# LT-33222-L_v1_0.net
KiCad netlist of a schematic drawn in EAGLE
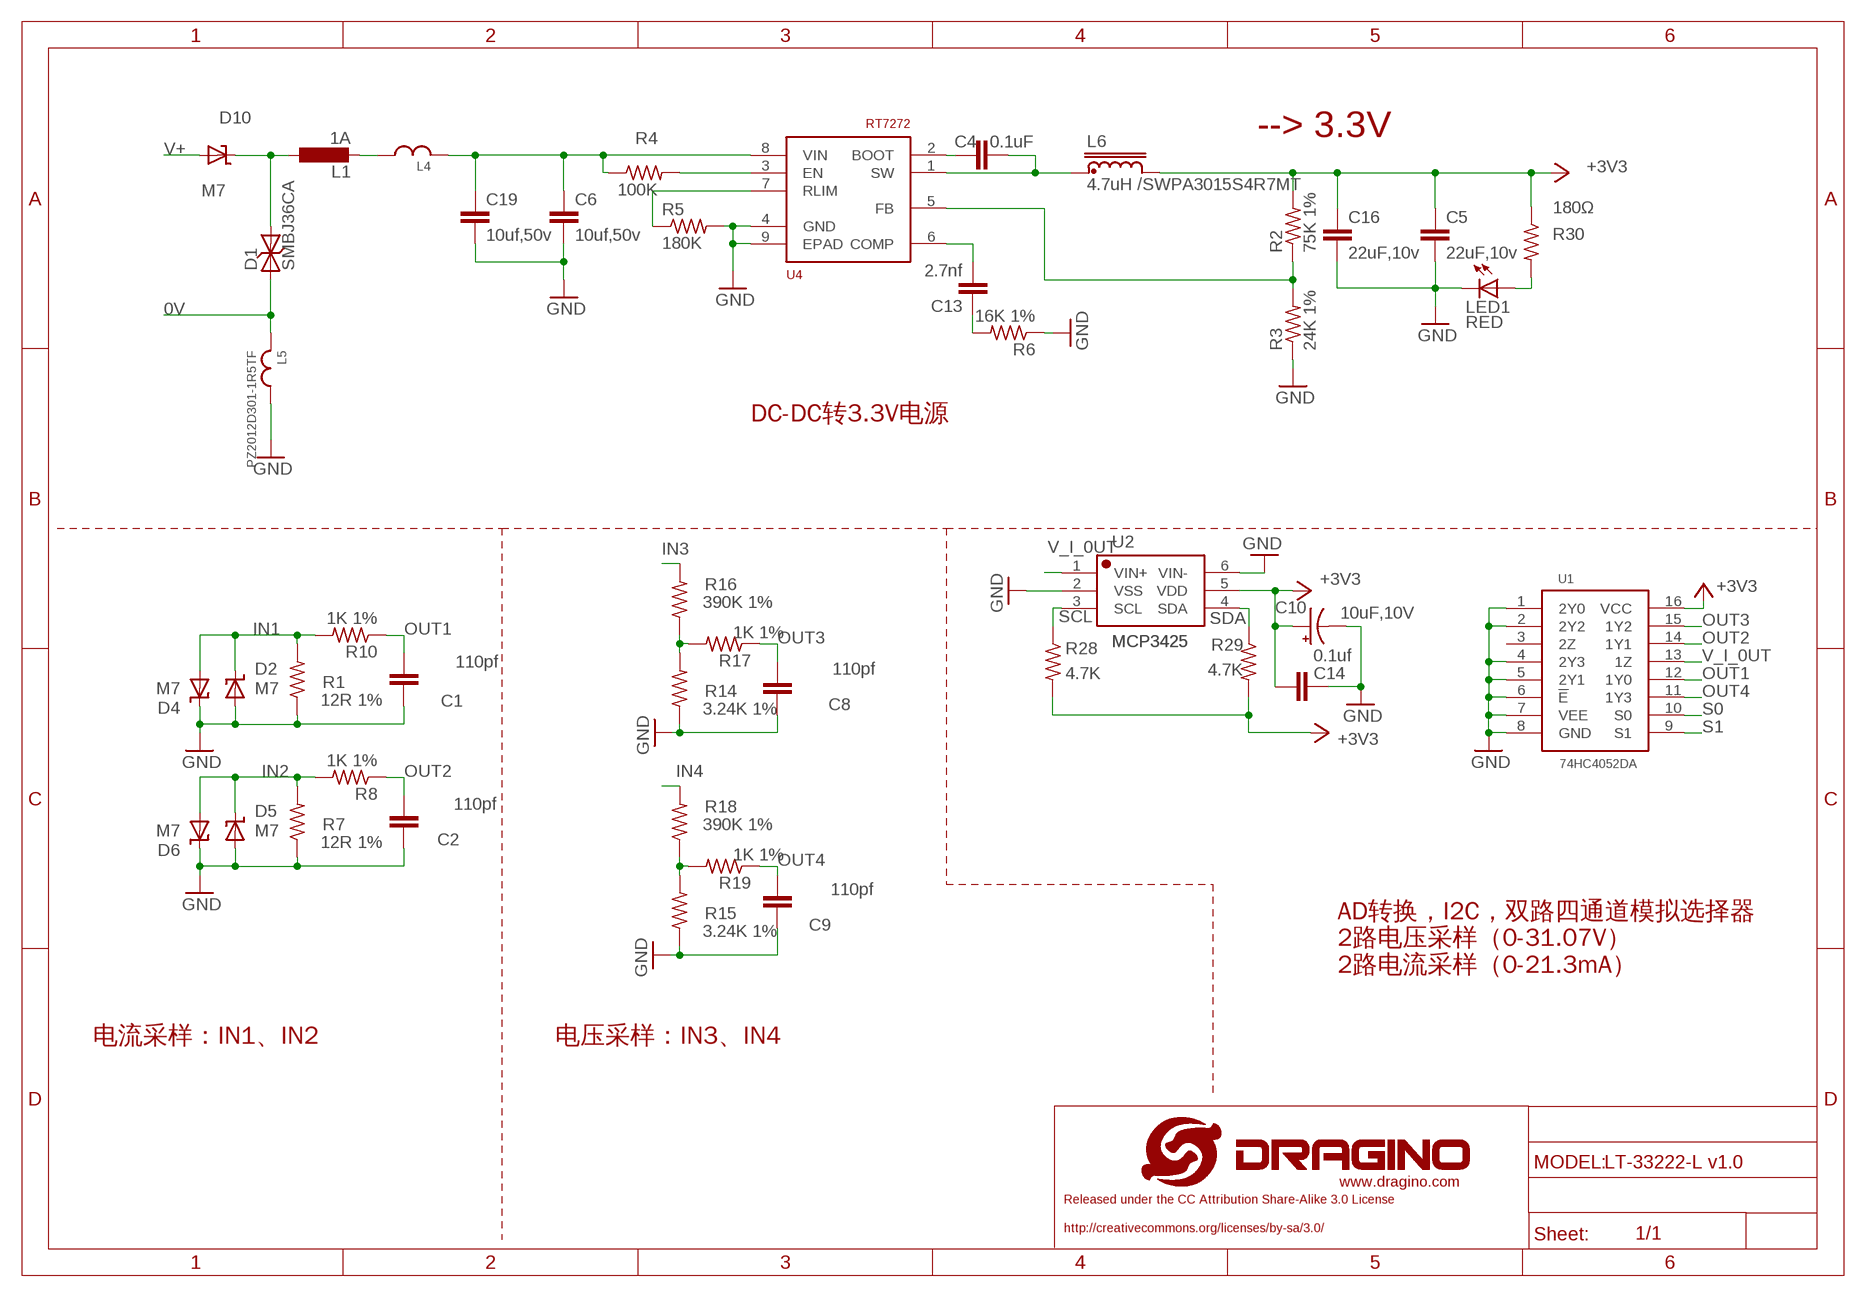
[diagram p0: schematic, sheet 1, part 1 of 2]
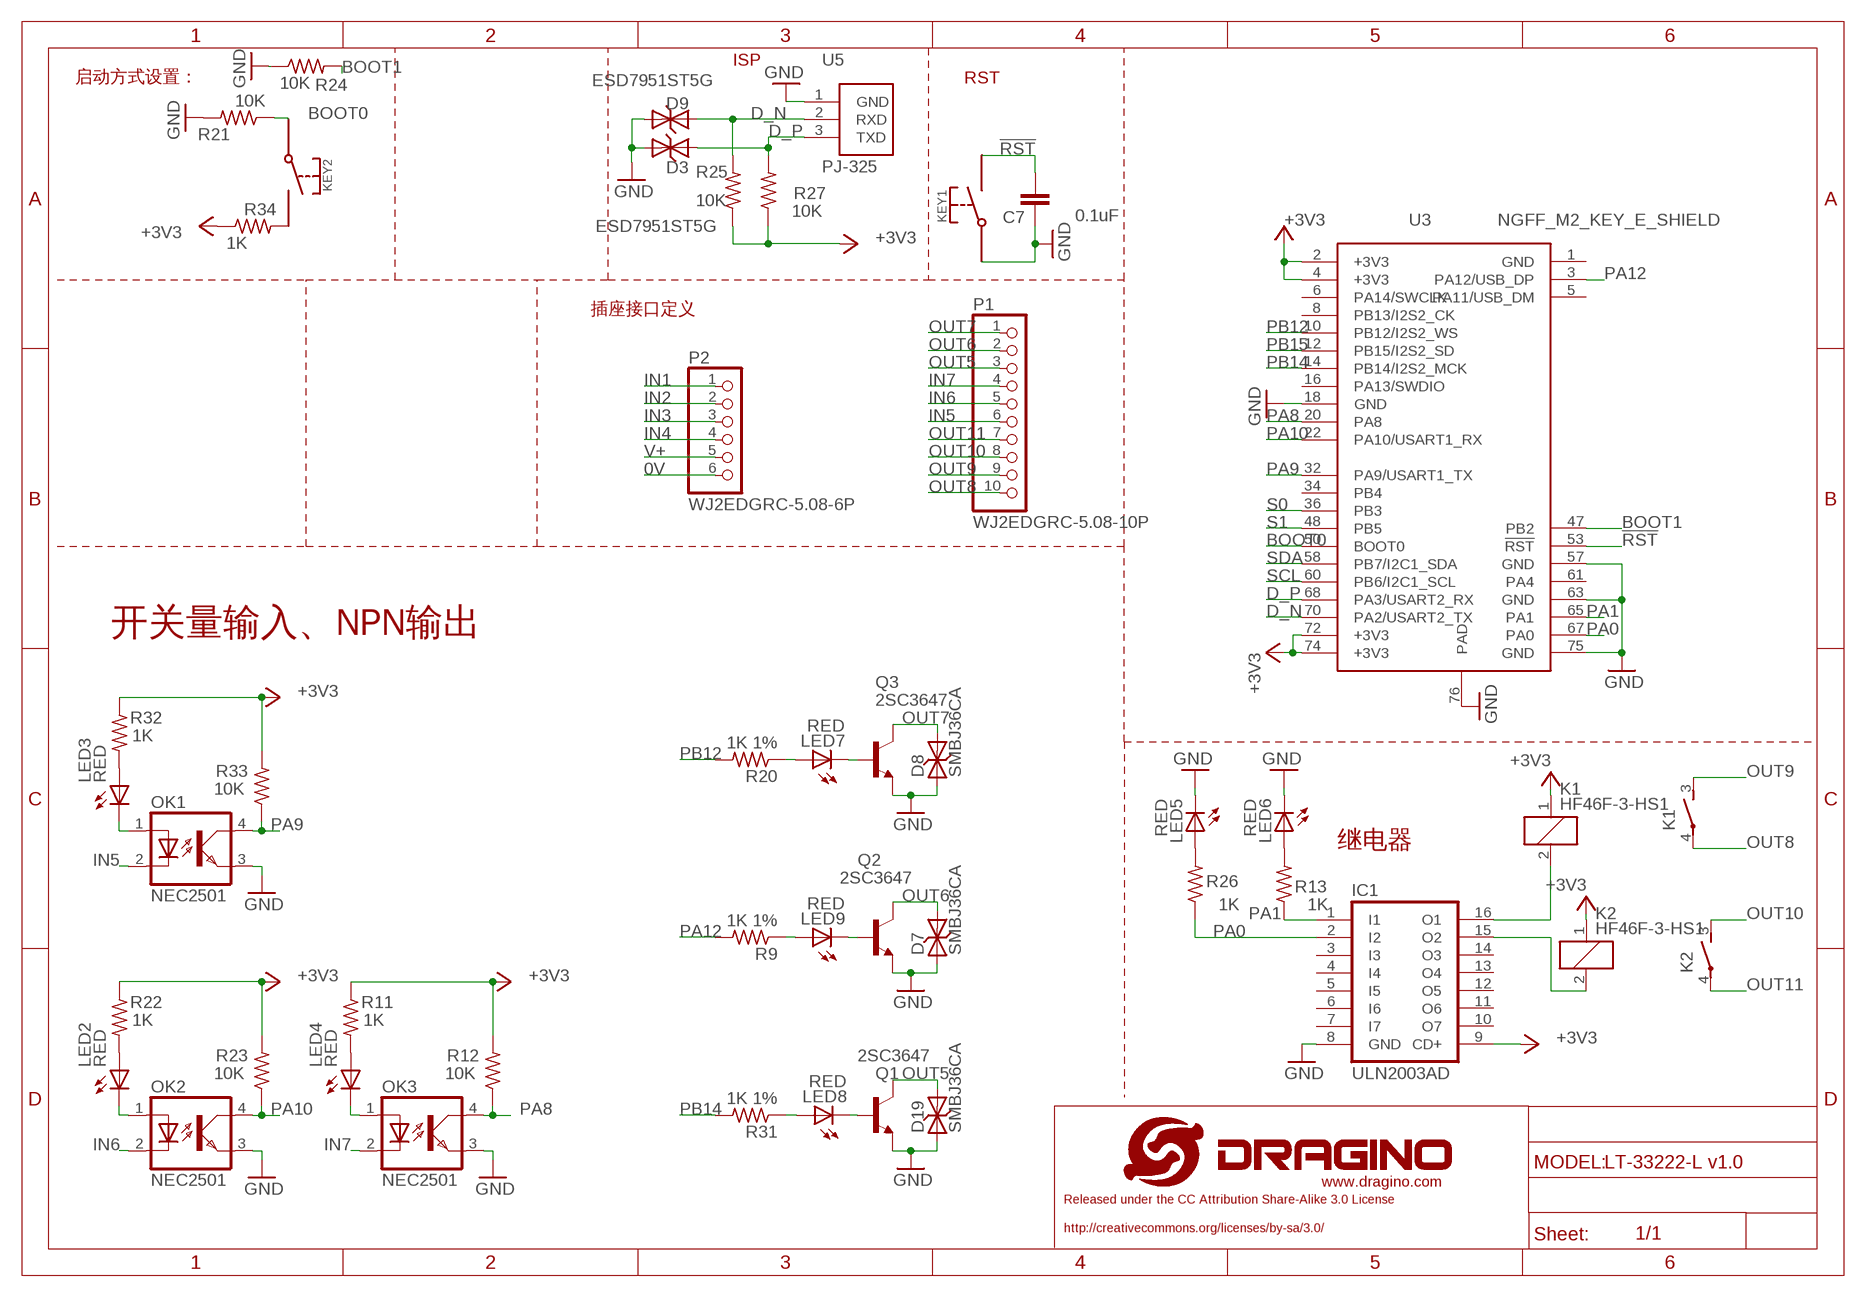
[diagram p1: schematic, sheet 1, part 2 of 2]

(export (version "E")
  (design (tool "Eeschema 10.0.6"))
  (components
    (comp (ref "C1")
      (value "110pf")
      (footprint "eagle-import:C0402")
      (libsource (lib "eagle-import") (part "C-EUC0402"))
    )
    (comp (ref "C2")
      (value "110pf")
      (footprint "eagle-import:C0402")
      (libsource (lib "eagle-import") (part "C-EUC0402"))
    )
    (comp (ref "C4")
      (value "0.1uF")
      (footprint "eagle-import:C0402")
      (libsource (lib "eagle-import") (part "C-EUC0402"))
    )
    (comp (ref "C5")
      (value "22uF,10v")
      (footprint "eagle-import:C1210")
      (libsource (lib "eagle-import") (part "C-EUC1210"))
    )
    (comp (ref "C6")
      (value "10uf,50v")
      (footprint "eagle-import:C1206")
      (libsource (lib "eagle-import") (part "C-EUC1206"))
    )
    (comp (ref "C7")
      (value "0.1uF")
      (footprint "eagle-import:C0402")
      (libsource (lib "eagle-import") (part "C-EUC0402"))
    )
    (comp (ref "C8")
      (value "110pf")
      (footprint "eagle-import:C0402")
      (libsource (lib "eagle-import") (part "C-EUC0402"))
    )
    (comp (ref "C9")
      (value "110pf")
      (footprint "eagle-import:C0402")
      (libsource (lib "eagle-import") (part "C-EUC0402"))
    )
    (comp (ref "C10")
      (value "10uF,10V")
      (footprint "eagle-import:SMC_A")
      (libsource (lib "eagle-import") (part "CPOL-USSMCA"))
    )
    (comp (ref "C13")
      (value "2.7nf")
      (footprint "eagle-import:C0402")
      (libsource (lib "eagle-import") (part "C-EUC0402"))
    )
    (comp (ref "C14")
      (value "0.1uf")
      (footprint "eagle-import:C0402")
      (libsource (lib "eagle-import") (part "C-EUC0402"))
    )
    (comp (ref "C16")
      (value "22uF,10v")
      (footprint "eagle-import:C1210")
      (libsource (lib "eagle-import") (part "C-EUC1210"))
    )
    (comp (ref "C19")
      (value "10uf,50v")
      (footprint "eagle-import:C1206")
      (libsource (lib "eagle-import") (part "C-EUC1206"))
    )
    (comp (ref "D1")
      (value "SMBJ36CA")
      (footprint "eagle-import:DO-214AA")
      (libsource (lib "eagle-import") (part "TVSDIO-214AA"))
    )
    (comp (ref "D2")
      (value "M7")
      (footprint "eagle-import:DO214AC")
      (libsource (lib "eagle-import") (part "SCHOTTKYSMBG"))
    )
    (comp (ref "D3")
      (value "ESD7951ST5G")
      (footprint "eagle-import:SOD−923")
      (libsource (lib "eagle-import") (part "TVSSOD−923"))
    )
    (comp (ref "D4")
      (value "M7")
      (footprint "eagle-import:DO214AC")
      (libsource (lib "eagle-import") (part "SCHOTTKYSMBG"))
    )
    (comp (ref "D5")
      (value "M7")
      (footprint "eagle-import:DO214AC")
      (libsource (lib "eagle-import") (part "SCHOTTKYSMBG"))
    )
    (comp (ref "D6")
      (value "M7")
      (footprint "eagle-import:DO214AC")
      (libsource (lib "eagle-import") (part "SCHOTTKYSMBG"))
    )
    (comp (ref "D7")
      (value "SMBJ36CA")
      (footprint "eagle-import:DO-214AA")
      (libsource (lib "eagle-import") (part "TVSDIO-214AA"))
    )
    (comp (ref "D8")
      (value "SMBJ36CA")
      (footprint "eagle-import:DO-214AA")
      (libsource (lib "eagle-import") (part "TVSDIO-214AA"))
    )
    (comp (ref "D9")
      (value "ESD7951ST5G")
      (footprint "eagle-import:SOD−923")
      (libsource (lib "eagle-import") (part "TVSSOD−923"))
    )
    (comp (ref "D10")
      (value "M7")
      (footprint "eagle-import:DO214AC")
      (libsource (lib "eagle-import") (part "SCHOTTKYSMBG"))
    )
    (comp (ref "D19")
      (value "SMBJ36CA")
      (footprint "eagle-import:DO-214AA")
      (libsource (lib "eagle-import") (part "TVSDIO-214AA"))
    )
    (comp (ref "IC1")
      (value "ULN2003AD")
      (footprint "eagle-import:SO16")
      (libsource (lib "eagle-import") (part "ULN2003AD"))
    )
    (comp (ref "K1")
      (value "HF46F-3-HS1")
      (footprint "eagle-import:HF46F-3-HS1")
      (libsource (lib "eagle-import") (part "HF46F-3-HS1"))
    )
    (comp (ref "K2")
      (value "HF46F-3-HS1")
      (footprint "eagle-import:HF46F-3-HS1")
      (libsource (lib "eagle-import") (part "HF46F-3-HS1"))
    )
    (comp (ref "KEY1")
      (value "SWITCHDIL4")
      (footprint "eagle-import:SWITCH_6X6X19_DIL4")
      (libsource (lib "eagle-import") (part "SWITCHDIL4"))
    )
    (comp (ref "KEY2")
      (value "SWITCHDIL4")
      (footprint "eagle-import:SWITCH_6X6X19_DIL4")
      (libsource (lib "eagle-import") (part "SWITCHDIL4"))
    )
    (comp (ref "L1")
      (value "1A")
      (footprint "eagle-import:L1812")
      (libsource (lib "eagle-import") (part "L-EUL1812"))
    )
    (comp (ref "L4")
      (value "PZ2012D301-1R5TF")
      (footprint "eagle-import:C2012")
      (libsource (lib "eagle-import") (part "BEADS"))
    )
    (comp (ref "L5")
      (value "PZ2012D301-1R5TF")
      (footprint "eagle-import:C0805")
      (libsource (lib "eagle-import") (part "BEADS0805"))
    )
    (comp (ref "L6")
      (value "4.7uH /SWPA3015S4R7MT")
      (footprint "eagle-import:SWPA3010S")
      (libsource (lib "eagle-import") (part "INDUCTORSWPA3010S"))
    )
    (comp (ref "LED1")
      (value "RED")
      (footprint "eagle-import:LED3MM")
      (libsource (lib "eagle-import") (part "LED3MM"))
    )
    (comp (ref "LED2")
      (value "RED")
      (footprint "eagle-import:LED3MM")
      (libsource (lib "eagle-import") (part "LED3MM"))
    )
    (comp (ref "LED3")
      (value "RED")
      (footprint "eagle-import:LED3MM")
      (libsource (lib "eagle-import") (part "LED3MM"))
    )
    (comp (ref "LED4")
      (value "RED")
      (footprint "eagle-import:LED3MM")
      (libsource (lib "eagle-import") (part "LED3MM"))
    )
    (comp (ref "LED5")
      (value "RED")
      (footprint "eagle-import:LED3MM")
      (libsource (lib "eagle-import") (part "LED3MM"))
    )
    (comp (ref "LED6")
      (value "RED")
      (footprint "eagle-import:LED3MM")
      (libsource (lib "eagle-import") (part "LED3MM"))
    )
    (comp (ref "LED7")
      (value "RED")
      (footprint "eagle-import:LED3MM")
      (libsource (lib "eagle-import") (part "LED3MM"))
    )
    (comp (ref "LED8")
      (value "RED")
      (footprint "eagle-import:LED3MM")
      (libsource (lib "eagle-import") (part "LED3MM"))
    )
    (comp (ref "LED9")
      (value "RED")
      (footprint "eagle-import:LED3MM")
      (libsource (lib "eagle-import") (part "LED3MM"))
    )
    (comp (ref "OK1")
      (value "NEC2501")
      (footprint "eagle-import:DIP4")
      (libsource (lib "eagle-import") (part "NEC2501"))
    )
    (comp (ref "OK2")
      (value "NEC2501")
      (footprint "eagle-import:DIP4")
      (libsource (lib "eagle-import") (part "NEC2501"))
    )
    (comp (ref "OK3")
      (value "NEC2501")
      (footprint "eagle-import:DIP4")
      (libsource (lib "eagle-import") (part "NEC2501"))
    )
    (comp (ref "P1")
      (value "WJ2EDGRC-5.08-10P")
      (footprint "eagle-import:WJ2EDGRC-5.08-10P")
      (libsource (lib "eagle-import") (part "WJ2EDGRC-5.08-10P"))
    )
    (comp (ref "P2")
      (value "WJ2EDGRC-5.08-6P")
      (footprint "eagle-import:WJ2EDGRC-5.08-6P")
      (libsource (lib "eagle-import") (part "WJ2EDGRC-5.08-6P"))
    )
    (comp (ref "Q1")
      (value "2SC3647")
      (footprint "eagle-import:SOT-89")
      (libsource (lib "eagle-import") (part "2SC3647"))
    )
    (comp (ref "Q2")
      (value "2SC3647")
      (footprint "eagle-import:SOT-89")
      (libsource (lib "eagle-import") (part "2SC3647"))
    )
    (comp (ref "Q3")
      (value "2SC3647")
      (footprint "eagle-import:SOT-89")
      (libsource (lib "eagle-import") (part "2SC3647"))
    )
    (comp (ref "R1")
      (value "12R 1%")
      (footprint "eagle-import:R1206")
      (libsource (lib "eagle-import") (part "R-US_R1206"))
    )
    (comp (ref "R2")
      (value "75K 1%")
      (footprint "eagle-import:R0402")
      (libsource (lib "eagle-import") (part "R-US_R0402"))
    )
    (comp (ref "R3")
      (value "24K 1%")
      (footprint "eagle-import:R0402")
      (libsource (lib "eagle-import") (part "R-US_R0402"))
    )
    (comp (ref "R4")
      (value "100K")
      (footprint "eagle-import:R0402")
      (libsource (lib "eagle-import") (part "R-US_R0402"))
    )
    (comp (ref "R5")
      (value "180K")
      (footprint "eagle-import:R0402")
      (libsource (lib "eagle-import") (part "R-US_R0402"))
    )
    (comp (ref "R6")
      (value "16K 1%")
      (footprint "eagle-import:R0402")
      (libsource (lib "eagle-import") (part "R-US_R0402"))
    )
    (comp (ref "R7")
      (value "12R 1%")
      (footprint "eagle-import:R1206")
      (libsource (lib "eagle-import") (part "R-US_R1206"))
    )
    (comp (ref "R8")
      (value "1K 1%")
      (footprint "eagle-import:R0402")
      (libsource (lib "eagle-import") (part "R-US_R0402"))
    )
    (comp (ref "R9")
      (value "1K 1%")
      (footprint "eagle-import:R0402")
      (libsource (lib "eagle-import") (part "R-US_R0402"))
    )
    (comp (ref "R10")
      (value "1K 1%")
      (footprint "eagle-import:R0402")
      (libsource (lib "eagle-import") (part "R-US_R0402"))
    )
    (comp (ref "R11")
      (value "1K")
      (footprint "eagle-import:R0402")
      (libsource (lib "eagle-import") (part "R-US_R0402"))
    )
    (comp (ref "R12")
      (value "10K")
      (footprint "eagle-import:R0402")
      (libsource (lib "eagle-import") (part "R-US_R0402"))
    )
    (comp (ref "R13")
      (value "1K")
      (footprint "eagle-import:R0402")
      (libsource (lib "eagle-import") (part "R-US_R0402"))
    )
    (comp (ref "R14")
      (value "3.24K 1%")
      (footprint "eagle-import:R1206")
      (libsource (lib "eagle-import") (part "R-US_R1206"))
    )
    (comp (ref "R15")
      (value "3.24K 1%")
      (footprint "eagle-import:R1206")
      (libsource (lib "eagle-import") (part "R-US_R1206"))
    )
    (comp (ref "R16")
      (value "390K 1%")
      (footprint "eagle-import:R1206")
      (libsource (lib "eagle-import") (part "R-US_R1206"))
    )
    (comp (ref "R17")
      (value "1K 1%")
      (footprint "eagle-import:R0402")
      (libsource (lib "eagle-import") (part "R-US_R0402"))
    )
    (comp (ref "R18")
      (value "390K 1%")
      (footprint "eagle-import:R1206")
      (libsource (lib "eagle-import") (part "R-US_R1206"))
    )
    (comp (ref "R19")
      (value "1K 1%")
      (footprint "eagle-import:R0402")
      (libsource (lib "eagle-import") (part "R-US_R0402"))
    )
    (comp (ref "R20")
      (value "1K 1%")
      (footprint "eagle-import:R0402")
      (libsource (lib "eagle-import") (part "R-US_R0402"))
    )
    (comp (ref "R21")
      (value "10K")
      (footprint "eagle-import:R0402")
      (libsource (lib "eagle-import") (part "R-US_R0402"))
    )
    (comp (ref "R22")
      (value "1K")
      (footprint "eagle-import:R0402")
      (libsource (lib "eagle-import") (part "R-US_R0402"))
    )
    (comp (ref "R23")
      (value "10K")
      (footprint "eagle-import:R0402")
      (libsource (lib "eagle-import") (part "R-US_R0402"))
    )
    (comp (ref "R24")
      (value "10K")
      (footprint "eagle-import:R0402")
      (libsource (lib "eagle-import") (part "R-US_R0402"))
    )
    (comp (ref "R25")
      (value "10K")
      (footprint "eagle-import:R0402")
      (libsource (lib "eagle-import") (part "R-US_R0402"))
    )
    (comp (ref "R26")
      (value "1K")
      (footprint "eagle-import:R0402")
      (libsource (lib "eagle-import") (part "R-US_R0402"))
    )
    (comp (ref "R27")
      (value "10K")
      (footprint "eagle-import:R0402")
      (libsource (lib "eagle-import") (part "R-US_R0402"))
    )
    (comp (ref "R28")
      (value "4.7K")
      (footprint "eagle-import:R0402")
      (libsource (lib "eagle-import") (part "R-US_R0402"))
    )
    (comp (ref "R29")
      (value "4.7K")
      (footprint "eagle-import:R0402")
      (libsource (lib "eagle-import") (part "R-US_R0402"))
    )
    (comp (ref "R30")
      (value "180Ω")
      (footprint "eagle-import:R0402")
      (libsource (lib "eagle-import") (part "R-US_R0402"))
    )
    (comp (ref "R31")
      (value "1K 1%")
      (footprint "eagle-import:R0402")
      (libsource (lib "eagle-import") (part "R-US_R0402"))
    )
    (comp (ref "R32")
      (value "1K")
      (footprint "eagle-import:R0402")
      (libsource (lib "eagle-import") (part "R-US_R0402"))
    )
    (comp (ref "R33")
      (value "10K")
      (footprint "eagle-import:R0402")
      (libsource (lib "eagle-import") (part "R-US_R0402"))
    )
    (comp (ref "R34")
      (value "1K")
      (footprint "eagle-import:R0402")
      (libsource (lib "eagle-import") (part "R-US_R0402"))
    )
    (comp (ref "U1")
      (value "74HC4052DA")
      (footprint "eagle-import:SO16")
      (libsource (lib "eagle-import") (part "74HC4052DA"))
    )
    (comp (ref "U2")
      (value "MCP3425")
      (footprint "eagle-import:6_SOT-23")
      (libsource (lib "eagle-import") (part "MCP3425"))
    )
    (comp (ref "U3")
      (value "NGFF_M2_KEY_E_SHIELD")
      (footprint "eagle-import:NGFF_M2_KEY_E_SHIELD")
      (libsource (lib "eagle-import") (part "NGFF_M2_KEY_E_SHIELD"))
    )
    (comp (ref "U4")
      (value "RT7272")
      (footprint "eagle-import:RT8250-SOP8")
      (libsource (lib "eagle-import") (part "RT7272"))
    )
    (comp (ref "U5")
      (value "PJ-325")
      (footprint "eagle-import:PJ-325")
      (libsource (lib "eagle-import") (part "PJ-325"))
    )
  )
  (nets
    (net (code "1") (name "+3V3") (class "Default")
      (node (ref "C10") (pin "+") (pinfunction "+_+") (pintype "passive"))
      (node (ref "C14") (pin "2") (pinfunction "2_2") (pintype "passive"))
      (node (ref "C16") (pin "1") (pinfunction "1_1") (pintype "passive"))
      (node (ref "C5") (pin "1") (pinfunction "1_1") (pintype "passive"))
      (node (ref "IC1") (pin "9") (pinfunction "CD+_9") (pintype "passive"))
      (node (ref "K1") (pin "1") (pinfunction "1_1") (pintype "passive"))
      (node (ref "K2") (pin "1") (pinfunction "1_1") (pintype "passive"))
      (node (ref "L6") (pin "P$2") (pinfunction "4_P$2") (pintype "passive"))
      (node (ref "R11") (pin "1") (pinfunction "1_1") (pintype "passive"))
      (node (ref "R12") (pin "2") (pinfunction "2_2") (pintype "passive"))
      (node (ref "R2") (pin "2") (pinfunction "2_2") (pintype "passive"))
      (node (ref "R22") (pin "1") (pinfunction "1_1") (pintype "passive"))
      (node (ref "R23") (pin "2") (pinfunction "2_2") (pintype "passive"))
      (node (ref "R25") (pin "1") (pinfunction "1_1") (pintype "passive"))
      (node (ref "R27") (pin "1") (pinfunction "1_1") (pintype "passive"))
      (node (ref "R28") (pin "2") (pinfunction "2_2") (pintype "passive"))
      (node (ref "R29") (pin "2") (pinfunction "2_2") (pintype "passive"))
      (node (ref "R30") (pin "1") (pinfunction "1_1") (pintype "passive"))
      (node (ref "R32") (pin "1") (pinfunction "1_1") (pintype "passive"))
      (node (ref "R33") (pin "2") (pinfunction "2_2") (pintype "passive"))
      (node (ref "R34") (pin "1") (pinfunction "1_1") (pintype "passive"))
      (node (ref "U1") (pin "16") (pinfunction "VCC_16") (pintype "power_in"))
      (node (ref "U2") (pin "5") (pinfunction "VDD_5") (pintype "power_in"))
      (node (ref "U3") (pin "2") (pinfunction "+3V3_2") (pintype "bidirectional"))
      (node (ref "U3") (pin "4") (pinfunction "+3V3_4") (pintype "bidirectional"))
      (node (ref "U3") (pin "72") (pinfunction "+3V3_72") (pintype "bidirectional"))
      (node (ref "U3") (pin "74") (pinfunction "+3V3_74") (pintype "bidirectional"))
    )
    (net (code "2") (name "/0V") (class "Default")
      (node (ref "D1") (pin "A") (pinfunction "1_A") (pintype "passive"))
      (node (ref "L5") (pin "1") (pinfunction "P$1_1") (pintype "bidirectional"))
      (node (ref "P2") (pin "6") (pinfunction "6_6") (pintype "passive"))
    )
    (net (code "3") (name "/BOOT0") (class "Default")
      (node (ref "KEY2") (pin "1") (pinfunction "P$1_1") (pintype "bidirectional"))
      (node (ref "R21") (pin "1") (pinfunction "1_1") (pintype "passive"))
      (node (ref "U3") (pin "50") (pinfunction "BOOT0_50") (pintype "bidirectional"))
    )
    (net (code "4") (name "/BOOT1") (class "Default")
      (node (ref "R24") (pin "2") (pinfunction "2_2") (pintype "passive"))
      (node (ref "U3") (pin "47") (pinfunction "PB2_47") (pintype "bidirectional"))
    )
    (net (code "5") (name "/D_N") (class "Default")
      (node (ref "D9") (pin "P$1") (pinfunction "1_P$1") (pintype "passive"))
      (node (ref "R25") (pin "2") (pinfunction "2_2") (pintype "passive"))
      (node (ref "U3") (pin "70") (pinfunction "PA2/USART2_TX_70") (pintype "bidirectional"))
      (node (ref "U5") (pin "2") (pinfunction "RXD_2") (pintype "bidirectional"))
    )
    (net (code "6") (name "/D_P") (class "Default")
      (node (ref "D3") (pin "P$1") (pinfunction "1_P$1") (pintype "passive"))
      (node (ref "R27") (pin "2") (pinfunction "2_2") (pintype "passive"))
      (node (ref "U3") (pin "68") (pinfunction "PA3/USART2_RX_68") (pintype "bidirectional"))
      (node (ref "U5") (pin "3") (pinfunction "TXD_3") (pintype "bidirectional"))
    )
    (net (code "7") (name "/IN1") (class "Default")
      (node (ref "D2") (pin "C") (pinfunction "C_C") (pintype "passive"))
      (node (ref "D4") (pin "A") (pinfunction "A_A") (pintype "passive"))
      (node (ref "P2") (pin "1") (pinfunction "1_1") (pintype "passive"))
      (node (ref "R1") (pin "2") (pinfunction "2_2") (pintype "passive"))
      (node (ref "R10") (pin "2") (pinfunction "2_2") (pintype "passive"))
    )
    (net (code "8") (name "/IN2") (class "Default")
      (node (ref "D5") (pin "C") (pinfunction "C_C") (pintype "passive"))
      (node (ref "D6") (pin "A") (pinfunction "A_A") (pintype "passive"))
      (node (ref "P2") (pin "2") (pinfunction "2_2") (pintype "passive"))
      (node (ref "R7") (pin "2") (pinfunction "2_2") (pintype "passive"))
      (node (ref "R8") (pin "2") (pinfunction "2_2") (pintype "passive"))
    )
    (net (code "9") (name "/IN3") (class "Default")
      (node (ref "P2") (pin "3") (pinfunction "3_3") (pintype "passive"))
      (node (ref "R16") (pin "2") (pinfunction "2_2") (pintype "passive"))
    )
    (net (code "10") (name "/IN4") (class "Default")
      (node (ref "P2") (pin "4") (pinfunction "4_4") (pintype "passive"))
      (node (ref "R18") (pin "2") (pinfunction "2_2") (pintype "passive"))
    )
    (net (code "11") (name "/IN5") (class "Default")
      (node (ref "OK1") (pin "2") (pinfunction "C_2") (pintype "passive"))
      (node (ref "P1") (pin "6") (pinfunction "6_6") (pintype "passive"))
    )
    (net (code "12") (name "/IN6") (class "Default")
      (node (ref "OK2") (pin "2") (pinfunction "C_2") (pintype "passive"))
      (node (ref "P1") (pin "5") (pinfunction "5_5") (pintype "passive"))
    )
    (net (code "13") (name "/IN7") (class "Default")
      (node (ref "OK3") (pin "2") (pinfunction "C_2") (pintype "passive"))
      (node (ref "P1") (pin "4") (pinfunction "4_4") (pintype "passive"))
    )
    (net (code "14") (name "/OUT1") (class "Default")
      (node (ref "C1") (pin "2") (pinfunction "2_2") (pintype "passive"))
      (node (ref "R10") (pin "1") (pinfunction "1_1") (pintype "passive"))
      (node (ref "U1") (pin "12") (pinfunction "1Y0_12") (pintype "bidirectional"))
    )
    (net (code "15") (name "/OUT2") (class "Default")
      (node (ref "C2") (pin "2") (pinfunction "2_2") (pintype "passive"))
      (node (ref "R8") (pin "1") (pinfunction "1_1") (pintype "passive"))
      (node (ref "U1") (pin "14") (pinfunction "1Y1_14") (pintype "bidirectional"))
    )
    (net (code "16") (name "/OUT3") (class "Default")
      (node (ref "C8") (pin "2") (pinfunction "2_2") (pintype "passive"))
      (node (ref "R17") (pin "1") (pinfunction "1_1") (pintype "passive"))
      (node (ref "U1") (pin "15") (pinfunction "1Y2_15") (pintype "bidirectional"))
    )
    (net (code "17") (name "/OUT4") (class "Default")
      (node (ref "C9") (pin "2") (pinfunction "2_2") (pintype "passive"))
      (node (ref "R19") (pin "1") (pinfunction "1_1") (pintype "passive"))
      (node (ref "U1") (pin "11") (pinfunction "1Y3_11") (pintype "bidirectional"))
    )
    (net (code "18") (name "/OUT5") (class "Default")
      (node (ref "D19") (pin "C") (pinfunction "2_C") (pintype "passive"))
      (node (ref "P1") (pin "3") (pinfunction "3_3") (pintype "passive"))
      (node (ref "Q1") (pin "C") (pinfunction "C_C") (pintype "passive"))
      (node (ref "Q1") (pin "C@1") (pinfunction "C_C@1") (pintype "passive"))
    )
    (net (code "19") (name "/OUT6") (class "Default")
      (node (ref "D7") (pin "C") (pinfunction "2_C") (pintype "passive"))
      (node (ref "P1") (pin "2") (pinfunction "2_2") (pintype "passive"))
      (node (ref "Q2") (pin "C") (pinfunction "C_C") (pintype "passive"))
      (node (ref "Q2") (pin "C@1") (pinfunction "C_C@1") (pintype "passive"))
    )
    (net (code "20") (name "/OUT7") (class "Default")
      (node (ref "D8") (pin "C") (pinfunction "2_C") (pintype "passive"))
      (node (ref "P1") (pin "1") (pinfunction "1_1") (pintype "passive"))
      (node (ref "Q3") (pin "C") (pinfunction "C_C") (pintype "passive"))
      (node (ref "Q3") (pin "C@1") (pinfunction "C_C@1") (pintype "passive"))
    )
    (net (code "21") (name "/OUT8") (class "Default")
      (node (ref "K1") (pin "4") (pinfunction "P_4") (pintype "passive"))
      (node (ref "P1") (pin "10") (pinfunction "10_10") (pintype "passive"))
    )
    (net (code "22") (name "/OUT9") (class "Default")
      (node (ref "K1") (pin "3") (pinfunction "S_3") (pintype "passive"))
      (node (ref "P1") (pin "9") (pinfunction "9_9") (pintype "passive"))
    )
    (net (code "23") (name "/OUT10") (class "Default")
      (node (ref "K2") (pin "3") (pinfunction "S_3") (pintype "passive"))
      (node (ref "P1") (pin "8") (pinfunction "8_8") (pintype "passive"))
    )
    (net (code "24") (name "/OUT11") (class "Default")
      (node (ref "K2") (pin "4") (pinfunction "P_4") (pintype "passive"))
      (node (ref "P1") (pin "7") (pinfunction "7_7") (pintype "passive"))
    )
    (net (code "25") (name "/PA0") (class "Default")
      (node (ref "IC1") (pin "2") (pinfunction "I2_2") (pintype "input"))
      (node (ref "R26") (pin "1") (pinfunction "1_1") (pintype "passive"))
      (node (ref "U3") (pin "67") (pinfunction "PA0_67") (pintype "bidirectional"))
    )
    (net (code "26") (name "/PA1") (class "Default")
      (node (ref "IC1") (pin "1") (pinfunction "I1_1") (pintype "input"))
      (node (ref "R13") (pin "1") (pinfunction "1_1") (pintype "passive"))
      (node (ref "U3") (pin "65") (pinfunction "PA1_65") (pintype "bidirectional"))
    )
    (net (code "27") (name "/PA8") (class "Default")
      (node (ref "OK3") (pin "4") (pinfunction "COL_4") (pintype "passive"))
      (node (ref "R12") (pin "1") (pinfunction "1_1") (pintype "passive"))
      (node (ref "U3") (pin "20") (pinfunction "PA8_20") (pintype "bidirectional"))
    )
    (net (code "28") (name "/PA9") (class "Default")
      (node (ref "OK1") (pin "4") (pinfunction "COL_4") (pintype "passive"))
      (node (ref "R33") (pin "1") (pinfunction "1_1") (pintype "passive"))
      (node (ref "U3") (pin "32") (pinfunction "PA9/USART1_TX_32") (pintype "bidirectional"))
    )
    (net (code "29") (name "/PA10") (class "Default")
      (node (ref "OK2") (pin "4") (pinfunction "COL_4") (pintype "passive"))
      (node (ref "R23") (pin "1") (pinfunction "1_1") (pintype "passive"))
      (node (ref "U3") (pin "22") (pinfunction "PA10/USART1_RX_22") (pintype "bidirectional"))
    )
    (net (code "30") (name "/PA12") (class "Default")
      (node (ref "R9") (pin "2") (pinfunction "2_2") (pintype "passive"))
      (node (ref "U3") (pin "3") (pinfunction "PA12/USB_DP_3") (pintype "bidirectional"))
    )
    (net (code "31") (name "/PB12") (class "Default")
      (node (ref "R20") (pin "2") (pinfunction "2_2") (pintype "passive"))
      (node (ref "U3") (pin "10") (pinfunction "PB12/I2S2_WS_10") (pintype "bidirectional"))
    )
    (net (code "32") (name "/PB14") (class "Default")
      (node (ref "R31") (pin "2") (pinfunction "2_2") (pintype "passive"))
      (node (ref "U3") (pin "14") (pinfunction "PB14/I2S2_MCK_14") (pintype "bidirectional"))
    )
    (net (code "33") (name "/PB15") (class "Default")
      (node (ref "U3") (pin "12") (pinfunction "PB15/I2S2_SD_12") (pintype "bidirectional"))
    )
    (net (code "34") (name "/S0") (class "Default")
      (node (ref "U1") (pin "10") (pinfunction "S0_10") (pintype "bidirectional"))
      (node (ref "U3") (pin "36") (pinfunction "PB3_36") (pintype "bidirectional"))
    )
    (net (code "35") (name "/S1") (class "Default")
      (node (ref "U1") (pin "9") (pinfunction "S1_9") (pintype "bidirectional"))
      (node (ref "U3") (pin "48") (pinfunction "PB5_48") (pintype "bidirectional"))
    )
    (net (code "36") (name "/SCL") (class "Default")
      (node (ref "R28") (pin "1") (pinfunction "1_1") (pintype "passive"))
      (node (ref "U2") (pin "3") (pinfunction "SCL_3") (pintype "input"))
      (node (ref "U3") (pin "60") (pinfunction "PB6/I2C1_SCL_60") (pintype "bidirectional"))
    )
    (net (code "37") (name "/SDA") (class "Default")
      (node (ref "R29") (pin "1") (pinfunction "1_1") (pintype "passive"))
      (node (ref "U2") (pin "4") (pinfunction "SDA_4") (pintype "input"))
      (node (ref "U3") (pin "58") (pinfunction "PB7/I2C1_SDA_58") (pintype "bidirectional"))
    )
    (net (code "38") (name "/V+") (class "Default")
      (node (ref "D10") (pin "A") (pinfunction "A_A") (pintype "passive"))
      (node (ref "P2") (pin "5") (pinfunction "5_5") (pintype "passive"))
    )
    (net (code "39") (name "/V_I_0UT") (class "Default")
      (node (ref "U1") (pin "13") (pinfunction "1Z_13") (pintype "output"))
      (node (ref "U2") (pin "1") (pinfunction "VIN+_1") (pintype "input"))
    )
    (net (code "40") (name "/~{RST}") (class "Default")
      (node (ref "C7") (pin "2") (pinfunction "2_2") (pintype "passive"))
      (node (ref "KEY1") (pin "2") (pinfunction "P$2_2") (pintype "bidirectional"))
      (node (ref "U3") (pin "53") (pinfunction "~{RST}_53") (pintype "bidirectional"))
    )
    (net (code "41") (name "GND") (class "Default")
      (node (ref "C1") (pin "1") (pinfunction "1_1") (pintype "passive"))
      (node (ref "C10") (pin "-") (pinfunction "-_-") (pintype "passive"))
      (node (ref "C14") (pin "1") (pinfunction "1_1") (pintype "passive"))
      (node (ref "C16") (pin "2") (pinfunction "2_2") (pintype "passive"))
      (node (ref "C19") (pin "2") (pinfunction "2_2") (pintype "passive"))
      (node (ref "C2") (pin "1") (pinfunction "1_1") (pintype "passive"))
      (node (ref "C5") (pin "2") (pinfunction "2_2") (pintype "passive"))
      (node (ref "C6") (pin "2") (pinfunction "2_2") (pintype "passive"))
      (node (ref "C7") (pin "1") (pinfunction "1_1") (pintype "passive"))
      (node (ref "C8") (pin "1") (pinfunction "1_1") (pintype "passive"))
      (node (ref "C9") (pin "1") (pinfunction "1_1") (pintype "passive"))
      (node (ref "D19") (pin "A") (pinfunction "1_A") (pintype "passive"))
      (node (ref "D2") (pin "A") (pinfunction "A_A") (pintype "passive"))
      (node (ref "D3") (pin "P$2") (pinfunction "2_P$2") (pintype "passive"))
      (node (ref "D4") (pin "C") (pinfunction "C_C") (pintype "passive"))
      (node (ref "D5") (pin "A") (pinfunction "A_A") (pintype "passive"))
      (node (ref "D6") (pin "C") (pinfunction "C_C") (pintype "passive"))
      (node (ref "D7") (pin "A") (pinfunction "1_A") (pintype "passive"))
      (node (ref "D8") (pin "A") (pinfunction "1_A") (pintype "passive"))
      (node (ref "D9") (pin "P$2") (pinfunction "2_P$2") (pintype "passive"))
      (node (ref "IC1") (pin "8") (pinfunction "GND_8") (pintype "power_in"))
      (node (ref "KEY1") (pin "1") (pinfunction "P$1_1") (pintype "bidirectional"))
      (node (ref "L5") (pin "2") (pinfunction "P$2_2") (pintype "bidirectional"))
      (node (ref "LED1") (pin "K") (pinfunction "C_K") (pintype "passive"))
      (node (ref "LED5") (pin "K") (pinfunction "C_K") (pintype "passive"))
      (node (ref "LED6") (pin "K") (pinfunction "C_K") (pintype "passive"))
      (node (ref "OK1") (pin "3") (pinfunction "EMIT_3") (pintype "passive"))
      (node (ref "OK2") (pin "3") (pinfunction "EMIT_3") (pintype "passive"))
      (node (ref "OK3") (pin "3") (pinfunction "EMIT_3") (pintype "passive"))
      (node (ref "Q1") (pin "E") (pinfunction "E_E") (pintype "passive"))
      (node (ref "Q2") (pin "E") (pinfunction "E_E") (pintype "passive"))
      (node (ref "Q3") (pin "E") (pinfunction "E_E") (pintype "passive"))
      (node (ref "R1") (pin "1") (pinfunction "1_1") (pintype "passive"))
      (node (ref "R14") (pin "1") (pinfunction "1_1") (pintype "passive"))
      (node (ref "R15") (pin "1") (pinfunction "1_1") (pintype "passive"))
      (node (ref "R21") (pin "2") (pinfunction "2_2") (pintype "passive"))
      (node (ref "R24") (pin "1") (pinfunction "1_1") (pintype "passive"))
      (node (ref "R3") (pin "1") (pinfunction "1_1") (pintype "passive"))
      (node (ref "R5") (pin "2") (pinfunction "2_2") (pintype "passive"))
      (node (ref "R6") (pin "1") (pinfunction "1_1") (pintype "passive"))
      (node (ref "R7") (pin "1") (pinfunction "1_1") (pintype "passive"))
      (node (ref "U1") (pin "1") (pinfunction "2Y0_1") (pintype "bidirectional"))
      (node (ref "U1") (pin "2") (pinfunction "2Y2_2") (pintype "bidirectional"))
      (node (ref "U1") (pin "4") (pinfunction "2Y3_4") (pintype "bidirectional"))
      (node (ref "U1") (pin "5") (pinfunction "2Y1_5") (pintype "bidirectional"))
      (node (ref "U1") (pin "6") (pinfunction "~{E}_6") (pintype "bidirectional"))
      (node (ref "U1") (pin "7") (pinfunction "VEE_7") (pintype "power_in"))
      (node (ref "U1") (pin "8") (pinfunction "GND_8") (pintype "power_in"))
      (node (ref "U2") (pin "2") (pinfunction "VSS_2") (pintype "power_in"))
      (node (ref "U2") (pin "6") (pinfunction "VIN-_6") (pintype "input"))
      (node (ref "U3") (pin "18") (pinfunction "GND_18") (pintype "bidirectional"))
      (node (ref "U3") (pin "57") (pinfunction "GND_57") (pintype "bidirectional"))
      (node (ref "U3") (pin "63") (pinfunction "GND_63") (pintype "bidirectional"))
      (node (ref "U3") (pin "75") (pinfunction "GND_75") (pintype "bidirectional"))
      (node (ref "U3") (pin "76") (pinfunction "PAD_76") (pintype "bidirectional"))
      (node (ref "U4") (pin "4") (pinfunction "GND_4") (pintype "bidirectional"))
      (node (ref "U4") (pin "9") (pinfunction "EPAD_9") (pintype "bidirectional"))
      (node (ref "U5") (pin "1") (pinfunction "GND_1") (pintype "bidirectional"))
    )
    (net (code "42") (name "Net-(C13-Pad1)") (class "Default")
      (node (ref "C13") (pin "1") (pinfunction "1_1") (pintype "passive"))
      (node (ref "R6") (pin "2") (pinfunction "2_2") (pintype "passive"))
    )
    (net (code "43") (name "Net-(D1-2)") (class "Default")
      (node (ref "D1") (pin "C") (pinfunction "2_C") (pintype "passive"))
      (node (ref "D10") (pin "C") (pinfunction "C_C") (pintype "passive"))
      (node (ref "L1") (pin "1") (pinfunction "1_1") (pintype "passive"))
    )
    (net (code "44") (name "Net-(IC1-O1)") (class "Default")
      (node (ref "IC1") (pin "16") (pinfunction "O1_16") (pintype "open_collector"))
      (node (ref "K1") (pin "2") (pinfunction "2_2") (pintype "passive"))
    )
    (net (code "45") (name "Net-(IC1-O2)") (class "Default")
      (node (ref "IC1") (pin "15") (pinfunction "O2_15") (pintype "open_collector"))
      (node (ref "K2") (pin "2") (pinfunction "2_2") (pintype "passive"))
    )
    (net (code "46") (name "Net-(KEY2-P$2)") (class "Default")
      (node (ref "KEY2") (pin "2") (pinfunction "P$2_2") (pintype "bidirectional"))
      (node (ref "R34") (pin "2") (pinfunction "2_2") (pintype "passive"))
    )
    (net (code "47") (name "Net-(L4-P$1)") (class "Default")
      (node (ref "C19") (pin "1") (pinfunction "1_1") (pintype "passive"))
      (node (ref "C6") (pin "1") (pinfunction "1_1") (pintype "passive"))
      (node (ref "L4") (pin "1") (pinfunction "P$1_1") (pintype "bidirectional"))
      (node (ref "R4") (pin "1") (pinfunction "1_1") (pintype "passive"))
      (node (ref "U4") (pin "8") (pinfunction "VIN_8") (pintype "bidirectional"))
    )
    (net (code "48") (name "Net-(L4-P$2)") (class "Default")
      (node (ref "L1") (pin "2") (pinfunction "2_2") (pintype "passive"))
      (node (ref "L4") (pin "2") (pinfunction "P$2_2") (pintype "bidirectional"))
    )
    (net (code "49") (name "Net-(L6-1)") (class "Default")
      (node (ref "C4") (pin "2") (pinfunction "2_2") (pintype "passive"))
      (node (ref "L6") (pin "P$1") (pinfunction "1_P$1") (pintype "passive"))
      (node (ref "U4") (pin "1") (pinfunction "SW_1") (pintype "bidirectional"))
    )
    (net (code "50") (name "Net-(LED1-PadA)") (class "Default")
      (node (ref "LED1") (pin "A") (pinfunction "A_A") (pintype "passive"))
      (node (ref "R30") (pin "2") (pinfunction "2_2") (pintype "passive"))
    )
    (net (code "51") (name "Net-(LED2-C)") (class "Default")
      (node (ref "LED2") (pin "K") (pinfunction "C_K") (pintype "passive"))
      (node (ref "OK2") (pin "1") (pinfunction "A_1") (pintype "passive"))
    )
    (net (code "52") (name "Net-(LED2-PadA)") (class "Default")
      (node (ref "LED2") (pin "A") (pinfunction "A_A") (pintype "passive"))
      (node (ref "R22") (pin "2") (pinfunction "2_2") (pintype "passive"))
    )
    (net (code "53") (name "Net-(LED3-C)") (class "Default")
      (node (ref "LED3") (pin "K") (pinfunction "C_K") (pintype "passive"))
      (node (ref "OK1") (pin "1") (pinfunction "A_1") (pintype "passive"))
    )
    (net (code "54") (name "Net-(LED3-PadA)") (class "Default")
      (node (ref "LED3") (pin "A") (pinfunction "A_A") (pintype "passive"))
      (node (ref "R32") (pin "2") (pinfunction "2_2") (pintype "passive"))
    )
    (net (code "55") (name "Net-(LED4-C)") (class "Default")
      (node (ref "LED4") (pin "K") (pinfunction "C_K") (pintype "passive"))
      (node (ref "OK3") (pin "1") (pinfunction "A_1") (pintype "passive"))
    )
    (net (code "56") (name "Net-(LED4-PadA)") (class "Default")
      (node (ref "LED4") (pin "A") (pinfunction "A_A") (pintype "passive"))
      (node (ref "R11") (pin "2") (pinfunction "2_2") (pintype "passive"))
    )
    (net (code "57") (name "Net-(LED5-PadA)") (class "Default")
      (node (ref "LED5") (pin "A") (pinfunction "A_A") (pintype "passive"))
      (node (ref "R26") (pin "2") (pinfunction "2_2") (pintype "passive"))
    )
    (net (code "58") (name "Net-(LED6-PadA)") (class "Default")
      (node (ref "LED6") (pin "A") (pinfunction "A_A") (pintype "passive"))
      (node (ref "R13") (pin "2") (pinfunction "2_2") (pintype "passive"))
    )
    (net (code "59") (name "Net-(LED7-C)") (class "Default")
      (node (ref "LED7") (pin "K") (pinfunction "C_K") (pintype "passive"))
      (node (ref "Q3") (pin "B") (pinfunction "B_B") (pintype "passive"))
    )
    (net (code "60") (name "Net-(LED7-PadA)") (class "Default")
      (node (ref "LED7") (pin "A") (pinfunction "A_A") (pintype "passive"))
      (node (ref "R20") (pin "1") (pinfunction "1_1") (pintype "passive"))
    )
    (net (code "61") (name "Net-(LED8-C)") (class "Default")
      (node (ref "LED8") (pin "K") (pinfunction "C_K") (pintype "passive"))
      (node (ref "Q1") (pin "B") (pinfunction "B_B") (pintype "passive"))
    )
    (net (code "62") (name "Net-(LED8-PadA)") (class "Default")
      (node (ref "LED8") (pin "A") (pinfunction "A_A") (pintype "passive"))
      (node (ref "R31") (pin "1") (pinfunction "1_1") (pintype "passive"))
    )
    (net (code "63") (name "Net-(LED9-C)") (class "Default")
      (node (ref "LED9") (pin "K") (pinfunction "C_K") (pintype "passive"))
      (node (ref "Q2") (pin "B") (pinfunction "B_B") (pintype "passive"))
    )
    (net (code "64") (name "Net-(LED9-PadA)") (class "Default")
      (node (ref "LED9") (pin "A") (pinfunction "A_A") (pintype "passive"))
      (node (ref "R9") (pin "1") (pinfunction "1_1") (pintype "passive"))
    )
    (net (code "65") (name "Net-(R14-Pad2)") (class "Default")
      (node (ref "R14") (pin "2") (pinfunction "2_2") (pintype "passive"))
      (node (ref "R16") (pin "1") (pinfunction "1_1") (pintype "passive"))
      (node (ref "R17") (pin "2") (pinfunction "2_2") (pintype "passive"))
    )
    (net (code "66") (name "Net-(R15-Pad2)") (class "Default")
      (node (ref "R15") (pin "2") (pinfunction "2_2") (pintype "passive"))
      (node (ref "R18") (pin "1") (pinfunction "1_1") (pintype "passive"))
      (node (ref "R19") (pin "2") (pinfunction "2_2") (pintype "passive"))
    )
    (net (code "67") (name "Net-(U4-BOOT)") (class "Default")
      (node (ref "C4") (pin "1") (pinfunction "1_1") (pintype "passive"))
      (node (ref "U4") (pin "2") (pinfunction "BOOT_2") (pintype "bidirectional"))
    )
    (net (code "68") (name "Net-(U4-COMP)") (class "Default")
      (node (ref "C13") (pin "2") (pinfunction "2_2") (pintype "passive"))
      (node (ref "U4") (pin "6") (pinfunction "COMP_6") (pintype "bidirectional"))
    )
    (net (code "69") (name "Net-(U4-EN)") (class "Default")
      (node (ref "R4") (pin "2") (pinfunction "2_2") (pintype "passive"))
      (node (ref "U4") (pin "3") (pinfunction "EN_3") (pintype "bidirectional"))
    )
    (net (code "70") (name "Net-(U4-FB)") (class "Default")
      (node (ref "R2") (pin "1") (pinfunction "1_1") (pintype "passive"))
      (node (ref "R3") (pin "2") (pinfunction "2_2") (pintype "passive"))
      (node (ref "U4") (pin "5") (pinfunction "FB_5") (pintype "bidirectional"))
    )
    (net (code "71") (name "Net-(U4-RLIM)") (class "Default")
      (node (ref "R5") (pin "1") (pinfunction "1_1") (pintype "passive"))
      (node (ref "U4") (pin "7") (pinfunction "RLIM_7") (pintype "bidirectional"))
    )
    (net (code "72") (name "unconnected-(IC1-I3-Pad3)") (class "Default")
      (node (ref "IC1") (pin "3") (pinfunction "I3_3") (pintype "input"))
    )
    (net (code "73") (name "unconnected-(IC1-I4-Pad4)") (class "Default")
      (node (ref "IC1") (pin "4") (pinfunction "I4_4") (pintype "input"))
    )
    (net (code "74") (name "unconnected-(IC1-I5-Pad5)") (class "Default")
      (node (ref "IC1") (pin "5") (pinfunction "I5_5") (pintype "input"))
    )
    (net (code "75") (name "unconnected-(IC1-I6-Pad6)") (class "Default")
      (node (ref "IC1") (pin "6") (pinfunction "I6_6") (pintype "input"))
    )
    (net (code "76") (name "unconnected-(IC1-I7-Pad7)") (class "Default")
      (node (ref "IC1") (pin "7") (pinfunction "I7_7") (pintype "input"))
    )
    (net (code "77") (name "unconnected-(IC1-O3-Pad14)") (class "Default")
      (node (ref "IC1") (pin "14") (pinfunction "O3_14") (pintype "open_collector"))
    )
    (net (code "78") (name "unconnected-(IC1-O4-Pad13)") (class "Default")
      (node (ref "IC1") (pin "13") (pinfunction "O4_13") (pintype "open_collector"))
    )
    (net (code "79") (name "unconnected-(IC1-O5-Pad12)") (class "Default")
      (node (ref "IC1") (pin "12") (pinfunction "O5_12") (pintype "open_collector"))
    )
    (net (code "80") (name "unconnected-(IC1-O6-Pad11)") (class "Default")
      (node (ref "IC1") (pin "11") (pinfunction "O6_11") (pintype "open_collector"))
    )
    (net (code "81") (name "unconnected-(IC1-O7-Pad10)") (class "Default")
      (node (ref "IC1") (pin "10") (pinfunction "O7_10") (pintype "open_collector"))
    )
    (net (code "82") (name "unconnected-(U1-2Z-Pad3)") (class "Default")
      (node (ref "U1") (pin "3") (pinfunction "2Z_3") (pintype "output"))
    )
    (net (code "83") (name "unconnected-(U3-GND-Pad1)") (class "Default")
      (node (ref "U3") (pin "1") (pinfunction "GND_1") (pintype "bidirectional"))
    )
    (net (code "84") (name "unconnected-(U3-PA4-Pad61)") (class "Default")
      (node (ref "U3") (pin "61") (pinfunction "PA4_61") (pintype "bidirectional"))
    )
    (net (code "85") (name "unconnected-(U3-PA11{slash}USB_DM-Pad5)") (class "Default")
      (node (ref "U3") (pin "5") (pinfunction "PA11/USB_DM_5") (pintype "bidirectional"))
    )
    (net (code "86") (name "unconnected-(U3-PA13{slash}SWDIO-Pad16)") (class "Default")
      (node (ref "U3") (pin "16") (pinfunction "PA13/SWDIO_16") (pintype "bidirectional"))
    )
    (net (code "87") (name "unconnected-(U3-PA14{slash}SWCLK-Pad6)") (class "Default")
      (node (ref "U3") (pin "6") (pinfunction "PA14/SWCLK_6") (pintype "bidirectional"))
    )
    (net (code "88") (name "unconnected-(U3-PB4-Pad34)") (class "Default")
      (node (ref "U3") (pin "34") (pinfunction "PB4_34") (pintype "bidirectional"))
    )
    (net (code "89") (name "unconnected-(U3-PB13{slash}I2S2_CK-Pad8)") (class "Default")
      (node (ref "U3") (pin "8") (pinfunction "PB13/I2S2_CK_8") (pintype "bidirectional"))
    )
  )
)
